# Pimitachi.net
KiCad netlist of a schematic drawn in EAGLE
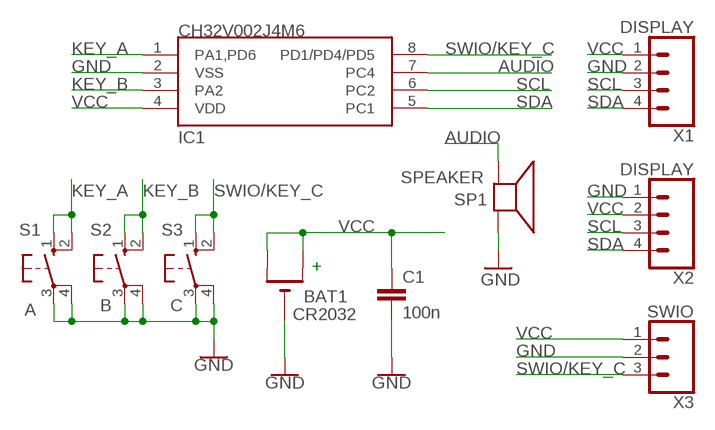
[diagram p0: schematic, sheet 1]

(export (version "E")
  (design (tool "Eeschema 10.0.6"))
  (components
    (comp (ref "BAT1")
      (value "CR2032")
      (footprint "eagle-import:CR2032-THRU")
      (libsource (lib "eagle-import") (part "CR2032THM"))
    )
    (comp (ref "C1")
      (value "100n")
      (footprint "eagle-import:C1206K")
      (libsource (lib "eagle-import") (part "C-EUC1206K"))
    )
    (comp (ref "IC1")
      (value "CH32V002J4M6")
      (footprint "eagle-import:SOP8")
      (libsource (lib "eagle-import") (part "CH32V003J4M6"))
    )
    (comp (ref "S1")
      (value "A")
      (footprint "eagle-import:B3F-10XX")
      (fields (field (name "MPN") "B3F-1000"))
      (libsource (lib "eagle-import") (part "10-XX"))
    )
    (comp (ref "S2")
      (value "B")
      (footprint "eagle-import:B3F-10XX")
      (fields (field (name "MPN") "B3F-1000"))
      (libsource (lib "eagle-import") (part "10-XX"))
    )
    (comp (ref "S3")
      (value "C")
      (footprint "eagle-import:B3F-10XX")
      (fields (field (name "MPN") "B3F-1000"))
      (libsource (lib "eagle-import") (part "10-XX"))
    )
    (comp (ref "SP1")
      (value "SPEAKER")
      (footprint "eagle-import:SPEAKER-PIEZO")
      (libsource (lib "eagle-import") (part "SPEAKERSPEAKER-PIEZO"))
    )
    (comp (ref "X1")
      (value "DISPLAY")
      (footprint "eagle-import:1X04")
      (libsource (lib "eagle-import") (part "CONN_04"))
    )
    (comp (ref "X2")
      (value "DISPLAY")
      (footprint "eagle-import:1X04")
      (libsource (lib "eagle-import") (part "CONN_04"))
    )
    (comp (ref "X3")
      (value "SWIO")
      (footprint "eagle-import:1X03_SMD_RA_MALE_POST_SMALLEST")
      (libsource (lib "eagle-import") (part "CONN_031X03_SMD_RA_MALE_POST_SMALLEST"))
    )
  )
  (nets
    (net (code "1") (name "/AUDIO") (class "Default")
      (node (ref "IC1") (pin "7") (pinfunction "PC4_7") (pintype "bidirectional"))
      (node (ref "SP1") (pin "1") (pinfunction "+_1") (pintype "passive"))
    )
    (net (code "2") (name "/KEY_A") (class "Default")
      (node (ref "IC1") (pin "1") (pinfunction "PA1,PD6_1") (pintype "bidirectional"))
      (node (ref "S1") (pin "1") (pinfunction "S_1") (pintype "passive"))
      (node (ref "S1") (pin "2") (pinfunction "S1_2") (pintype "passive"))
    )
    (net (code "3") (name "/KEY_B") (class "Default")
      (node (ref "IC1") (pin "3") (pinfunction "PA2_3") (pintype "bidirectional"))
      (node (ref "S2") (pin "1") (pinfunction "S_1") (pintype "passive"))
      (node (ref "S2") (pin "2") (pinfunction "S1_2") (pintype "passive"))
    )
    (net (code "4") (name "/SCL") (class "Default")
      (node (ref "IC1") (pin "6") (pinfunction "PC2_6") (pintype "bidirectional"))
      (node (ref "X1") (pin "3") (pinfunction "3_3") (pintype "passive"))
      (node (ref "X2") (pin "3") (pinfunction "3_3") (pintype "passive"))
    )
    (net (code "5") (name "/SDA") (class "Default")
      (node (ref "IC1") (pin "5") (pinfunction "PC1_5") (pintype "bidirectional"))
      (node (ref "X1") (pin "4") (pinfunction "4_4") (pintype "passive"))
      (node (ref "X2") (pin "4") (pinfunction "4_4") (pintype "passive"))
    )
    (net (code "6") (name "/SWIO{slash}KEY_C") (class "Default")
      (node (ref "IC1") (pin "8") (pinfunction "PD1/PD4/PD5_8") (pintype "bidirectional"))
      (node (ref "S3") (pin "1") (pinfunction "S_1") (pintype "passive"))
      (node (ref "S3") (pin "2") (pinfunction "S1_2") (pintype "passive"))
      (node (ref "X3") (pin "3") (pinfunction "3_3") (pintype "passive"))
    )
    (net (code "7") (name "/VCC") (class "Default")
      (node (ref "BAT1") (pin "+1") (pinfunction "+_+1") (pintype "passive"))
      (node (ref "BAT1") (pin "+2") (pinfunction "+1_+2") (pintype "passive"))
      (node (ref "C1") (pin "1") (pinfunction "1_1") (pintype "passive"))
      (node (ref "IC1") (pin "4") (pinfunction "VDD_4") (pintype "power_in"))
      (node (ref "X1") (pin "1") (pinfunction "1_1") (pintype "passive"))
      (node (ref "X2") (pin "2") (pinfunction "2_2") (pintype "passive"))
      (node (ref "X3") (pin "1") (pinfunction "1_1") (pintype "passive"))
    )
    (net (code "8") (name "GND") (class "Default")
      (node (ref "BAT1") (pin "-") (pinfunction "-_-") (pintype "passive"))
      (node (ref "C1") (pin "2") (pinfunction "2_2") (pintype "passive"))
      (node (ref "IC1") (pin "2") (pinfunction "VSS_2") (pintype "power_in"))
      (node (ref "S1") (pin "3") (pinfunction "P_3") (pintype "passive"))
      (node (ref "S1") (pin "4") (pinfunction "P1_4") (pintype "passive"))
      (node (ref "S2") (pin "3") (pinfunction "P_3") (pintype "passive"))
      (node (ref "S2") (pin "4") (pinfunction "P1_4") (pintype "passive"))
      (node (ref "S3") (pin "3") (pinfunction "P_3") (pintype "passive"))
      (node (ref "S3") (pin "4") (pinfunction "P1_4") (pintype "passive"))
      (node (ref "SP1") (pin "2") (pinfunction "-_2") (pintype "passive"))
      (node (ref "X1") (pin "2") (pinfunction "2_2") (pintype "passive"))
      (node (ref "X2") (pin "1") (pinfunction "1_1") (pintype "passive"))
      (node (ref "X3") (pin "2") (pinfunction "2_2") (pintype "passive"))
    )
  )
)
